# SCH_Control_Decoder_2021-10-07.net
KiCad netlist of a schematic drawn in EasyEDA
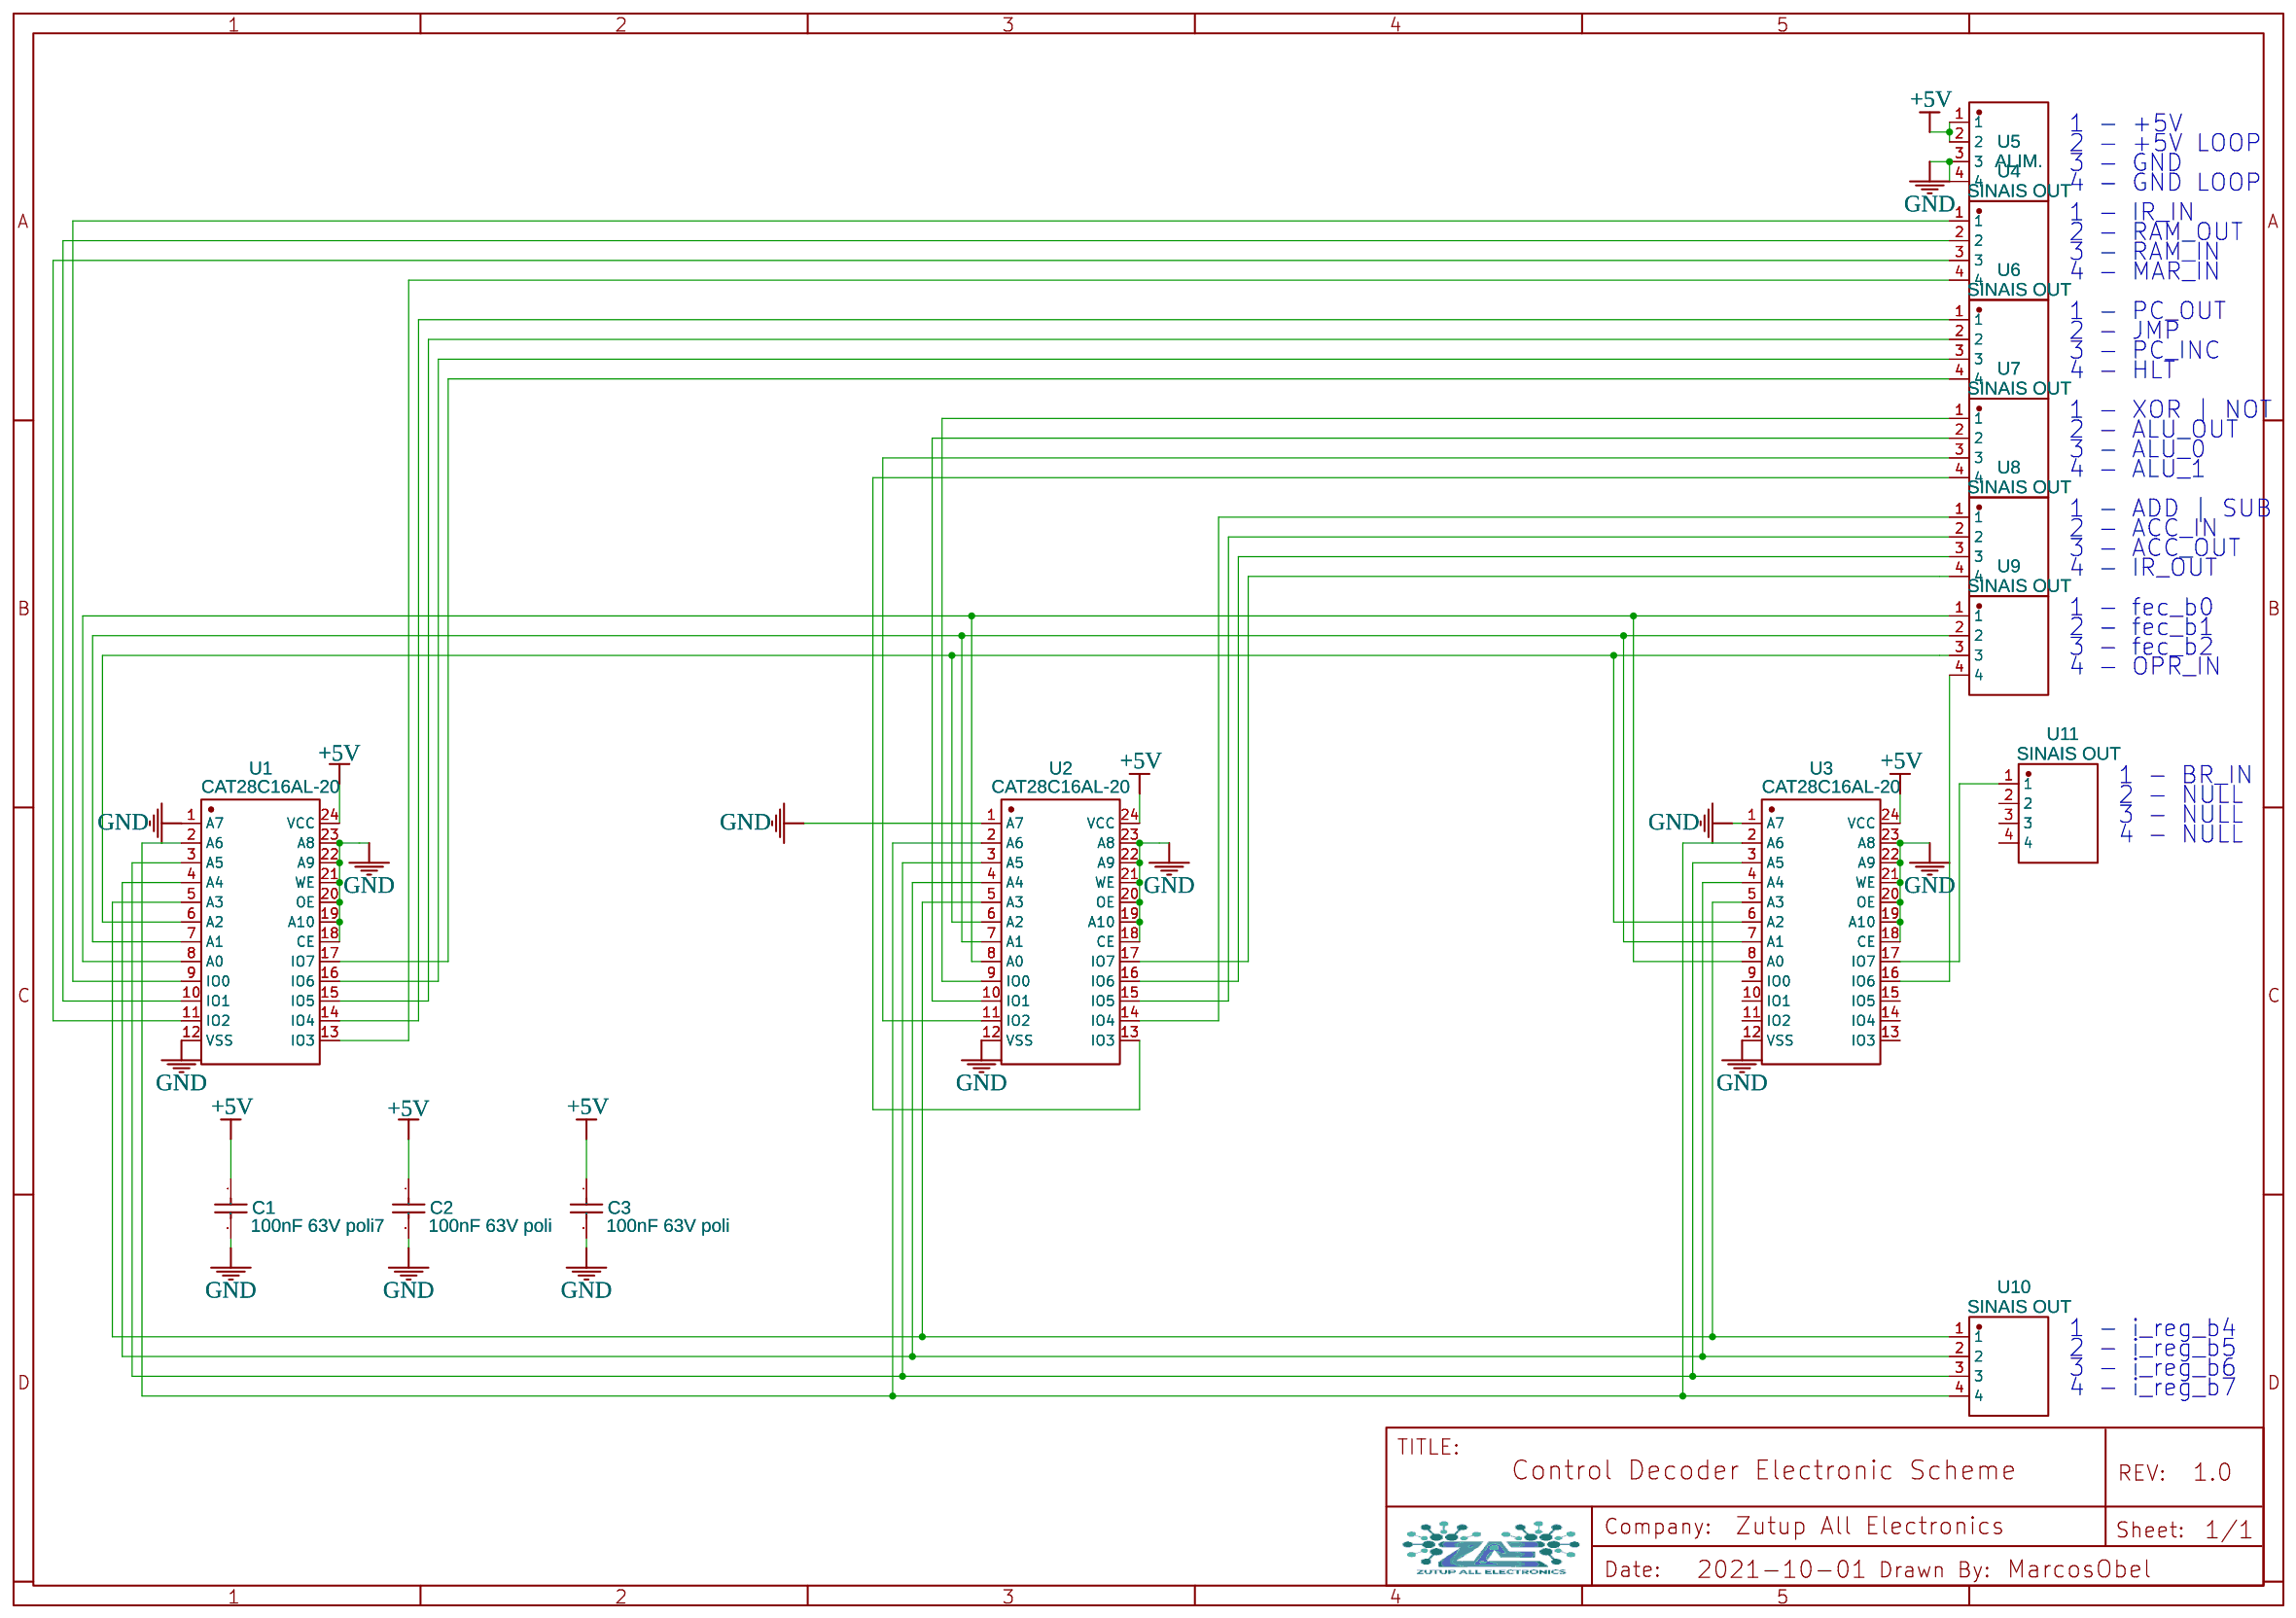
[diagram p0: schematic sheet]

(export (version "E")
  (design (tool "Eeschema 10.0.6"))
  (components
    (comp (ref "C1")
      (value "100nF 63V poli7")
      (fields
        (field (name "BOM_Manufacturer Part") "SR305C105KAR")
        (field (name "BOM_Supplier Part") "C444741")
      )
      (libsource (lib "") (part "SR305C105KAR"))
    )
    (comp (ref "C2")
      (value "100nF 63V poli")
      (fields
        (field (name "BOM_Manufacturer Part") "SR305C105KAR")
        (field (name "BOM_Supplier Part") "C444741")
      )
      (libsource (lib "") (part "SR305C105KAR"))
    )
    (comp (ref "C3")
      (value "100nF 63V poli")
      (fields
        (field (name "BOM_Manufacturer Part") "SR305C105KAR")
        (field (name "BOM_Supplier Part") "C444741")
      )
      (libsource (lib "") (part "SR305C105KAR"))
    )
    (comp (ref "U1") (value "CAT28C16AL-20") (libsource (lib "") (part "CAT28C16AL-20")))
    (comp (ref "U2") (value "CAT28C16AL-20") (libsource (lib "") (part "CAT28C16AL-20")))
    (comp (ref "U3") (value "CAT28C16AL-20") (libsource (lib "") (part "CAT28C16AL-20")))
    (comp (ref "U4")
      (value "SINAIS OUT")
      (fields (field (name "BOM_Manufacturer Part") "171825-4") (field (name "BOM_Supplier Part") "C210162"))
      (libsource (lib "") (part "171825-4"))
    )
    (comp (ref "U5")
      (value "ALIM.")
      (fields (field (name "BOM_Manufacturer Part") "171825-4") (field (name "BOM_Supplier Part") "C210162"))
      (libsource (lib "") (part "171825-4"))
    )
    (comp (ref "U6")
      (value "SINAIS OUT")
      (fields (field (name "BOM_Manufacturer Part") "171825-4") (field (name "BOM_Supplier Part") "C210162"))
      (libsource (lib "") (part "171825-4"))
    )
    (comp (ref "U7")
      (value "SINAIS OUT")
      (fields (field (name "BOM_Manufacturer Part") "171825-4") (field (name "BOM_Supplier Part") "C210162"))
      (libsource (lib "") (part "171825-4"))
    )
    (comp (ref "U8")
      (value "SINAIS OUT")
      (fields (field (name "BOM_Manufacturer Part") "171825-4") (field (name "BOM_Supplier Part") "C210162"))
      (libsource (lib "") (part "171825-4"))
    )
    (comp (ref "U9")
      (value "SINAIS OUT")
      (fields (field (name "BOM_Manufacturer Part") "171825-4") (field (name "BOM_Supplier Part") "C210162"))
      (libsource (lib "") (part "171825-4"))
    )
    (comp (ref "U10")
      (value "SINAIS OUT")
      (fields (field (name "BOM_Manufacturer Part") "171825-4") (field (name "BOM_Supplier Part") "C210162"))
      (libsource (lib "") (part "171825-4"))
    )
    (comp (ref "U11")
      (value "SINAIS OUT")
      (fields (field (name "BOM_Manufacturer Part") "171825-4") (field (name "BOM_Supplier Part") "C210162"))
      (libsource (lib "") (part "171825-4"))
    )
  )
  (nets
    (net (code "1") (name "+5V") (class "Default")
      (node (ref "C1") (pin "1") (pinfunction "1_1") (pintype "input"))
      (node (ref "C2") (pin "1") (pinfunction "1_1") (pintype "input"))
      (node (ref "C3") (pin "1") (pinfunction "1_1") (pintype "input"))
      (node (ref "U1") (pin "24") (pinfunction "VCC_24") (pintype "unspecified"))
      (node (ref "U2") (pin "24") (pinfunction "VCC_24") (pintype "unspecified"))
      (node (ref "U3") (pin "24") (pinfunction "VCC_24") (pintype "unspecified"))
      (node (ref "U5") (pin "1") (pinfunction "1_1") (pintype "unspecified"))
      (node (ref "U5") (pin "2") (pinfunction "2_2") (pintype "unspecified"))
    )
    (net (code "2") (name "GND") (class "Default")
      (node (ref "C1") (pin "2") (pinfunction "2_2") (pintype "input"))
      (node (ref "C2") (pin "2") (pinfunction "2_2") (pintype "input"))
      (node (ref "C3") (pin "2") (pinfunction "2_2") (pintype "input"))
      (node (ref "U1") (pin "1") (pinfunction "A7_1") (pintype "unspecified"))
      (node (ref "U1") (pin "12") (pinfunction "VSS_12") (pintype "unspecified"))
      (node (ref "U1") (pin "18") (pinfunction "CE_18") (pintype "unspecified"))
      (node (ref "U1") (pin "19") (pinfunction "A10_19") (pintype "unspecified"))
      (node (ref "U1") (pin "20") (pinfunction "OE_20") (pintype "unspecified"))
      (node (ref "U1") (pin "21") (pinfunction "WE_21") (pintype "unspecified"))
      (node (ref "U1") (pin "22") (pinfunction "A9_22") (pintype "unspecified"))
      (node (ref "U1") (pin "23") (pinfunction "A8_23") (pintype "unspecified"))
      (node (ref "U2") (pin "1") (pinfunction "A7_1") (pintype "unspecified"))
      (node (ref "U2") (pin "12") (pinfunction "VSS_12") (pintype "unspecified"))
      (node (ref "U2") (pin "18") (pinfunction "CE_18") (pintype "unspecified"))
      (node (ref "U2") (pin "19") (pinfunction "A10_19") (pintype "unspecified"))
      (node (ref "U2") (pin "20") (pinfunction "OE_20") (pintype "unspecified"))
      (node (ref "U2") (pin "21") (pinfunction "WE_21") (pintype "unspecified"))
      (node (ref "U2") (pin "22") (pinfunction "A9_22") (pintype "unspecified"))
      (node (ref "U2") (pin "23") (pinfunction "A8_23") (pintype "unspecified"))
      (node (ref "U3") (pin "1") (pinfunction "A7_1") (pintype "unspecified"))
      (node (ref "U3") (pin "12") (pinfunction "VSS_12") (pintype "unspecified"))
      (node (ref "U3") (pin "18") (pinfunction "CE_18") (pintype "unspecified"))
      (node (ref "U3") (pin "19") (pinfunction "A10_19") (pintype "unspecified"))
      (node (ref "U3") (pin "20") (pinfunction "OE_20") (pintype "unspecified"))
      (node (ref "U3") (pin "21") (pinfunction "WE_21") (pintype "unspecified"))
      (node (ref "U3") (pin "22") (pinfunction "A9_22") (pintype "unspecified"))
      (node (ref "U3") (pin "23") (pinfunction "A8_23") (pintype "unspecified"))
      (node (ref "U5") (pin "3") (pinfunction "3_3") (pintype "unspecified"))
      (node (ref "U5") (pin "4") (pinfunction "4_4") (pintype "unspecified"))
    )
    (net (code "3") (name "Net-(U1-A0)") (class "Default")
      (node (ref "U1") (pin "8") (pinfunction "A0_8") (pintype "unspecified"))
      (node (ref "U2") (pin "8") (pinfunction "A0_8") (pintype "unspecified"))
      (node (ref "U3") (pin "8") (pinfunction "A0_8") (pintype "unspecified"))
      (node (ref "U9") (pin "1") (pinfunction "1_1") (pintype "unspecified"))
    )
    (net (code "4") (name "Net-(U1-A1)") (class "Default")
      (node (ref "U1") (pin "7") (pinfunction "A1_7") (pintype "unspecified"))
      (node (ref "U2") (pin "7") (pinfunction "A1_7") (pintype "unspecified"))
      (node (ref "U3") (pin "7") (pinfunction "A1_7") (pintype "unspecified"))
      (node (ref "U9") (pin "2") (pinfunction "2_2") (pintype "unspecified"))
    )
    (net (code "5") (name "Net-(U1-A2)") (class "Default")
      (node (ref "U1") (pin "6") (pinfunction "A2_6") (pintype "unspecified"))
      (node (ref "U2") (pin "6") (pinfunction "A2_6") (pintype "unspecified"))
      (node (ref "U3") (pin "6") (pinfunction "A2_6") (pintype "unspecified"))
      (node (ref "U9") (pin "3") (pinfunction "3_3") (pintype "unspecified"))
    )
    (net (code "6") (name "Net-(U1-A3)") (class "Default")
      (node (ref "U1") (pin "5") (pinfunction "A3_5") (pintype "unspecified"))
      (node (ref "U10") (pin "1") (pinfunction "1_1") (pintype "unspecified"))
      (node (ref "U2") (pin "5") (pinfunction "A3_5") (pintype "unspecified"))
      (node (ref "U3") (pin "5") (pinfunction "A3_5") (pintype "unspecified"))
    )
    (net (code "7") (name "Net-(U1-A4)") (class "Default")
      (node (ref "U1") (pin "4") (pinfunction "A4_4") (pintype "unspecified"))
      (node (ref "U10") (pin "2") (pinfunction "2_2") (pintype "unspecified"))
      (node (ref "U2") (pin "4") (pinfunction "A4_4") (pintype "unspecified"))
      (node (ref "U3") (pin "4") (pinfunction "A4_4") (pintype "unspecified"))
    )
    (net (code "8") (name "Net-(U1-A5)") (class "Default")
      (node (ref "U1") (pin "3") (pinfunction "A5_3") (pintype "unspecified"))
      (node (ref "U10") (pin "3") (pinfunction "3_3") (pintype "unspecified"))
      (node (ref "U2") (pin "3") (pinfunction "A5_3") (pintype "unspecified"))
      (node (ref "U3") (pin "3") (pinfunction "A5_3") (pintype "unspecified"))
    )
    (net (code "9") (name "Net-(U1-A6)") (class "Default")
      (node (ref "U1") (pin "2") (pinfunction "A6_2") (pintype "unspecified"))
      (node (ref "U10") (pin "4") (pinfunction "4_4") (pintype "unspecified"))
      (node (ref "U2") (pin "2") (pinfunction "A6_2") (pintype "unspecified"))
      (node (ref "U3") (pin "2") (pinfunction "A6_2") (pintype "unspecified"))
    )
    (net (code "10") (name "Net-(U1-IO0)") (class "Default")
      (node (ref "U1") (pin "9") (pinfunction "IO0_9") (pintype "unspecified"))
      (node (ref "U4") (pin "1") (pinfunction "1_1") (pintype "unspecified"))
    )
    (net (code "11") (name "Net-(U1-IO1)") (class "Default")
      (node (ref "U1") (pin "10") (pinfunction "IO1_10") (pintype "unspecified"))
      (node (ref "U4") (pin "2") (pinfunction "2_2") (pintype "unspecified"))
    )
    (net (code "12") (name "Net-(U1-IO2)") (class "Default")
      (node (ref "U1") (pin "11") (pinfunction "IO2_11") (pintype "unspecified"))
      (node (ref "U4") (pin "3") (pinfunction "3_3") (pintype "unspecified"))
    )
    (net (code "13") (name "Net-(U1-IO3)") (class "Default")
      (node (ref "U1") (pin "13") (pinfunction "IO3_13") (pintype "unspecified"))
      (node (ref "U4") (pin "4") (pinfunction "4_4") (pintype "unspecified"))
    )
    (net (code "14") (name "Net-(U1-IO4)") (class "Default")
      (node (ref "U1") (pin "14") (pinfunction "IO4_14") (pintype "unspecified"))
      (node (ref "U6") (pin "1") (pinfunction "1_1") (pintype "unspecified"))
    )
    (net (code "15") (name "Net-(U1-IO5)") (class "Default")
      (node (ref "U1") (pin "15") (pinfunction "IO5_15") (pintype "unspecified"))
      (node (ref "U6") (pin "2") (pinfunction "2_2") (pintype "unspecified"))
    )
    (net (code "16") (name "Net-(U1-IO6)") (class "Default")
      (node (ref "U1") (pin "16") (pinfunction "IO6_16") (pintype "unspecified"))
      (node (ref "U6") (pin "3") (pinfunction "3_3") (pintype "unspecified"))
    )
    (net (code "17") (name "Net-(U1-IO7)") (class "Default")
      (node (ref "U1") (pin "17") (pinfunction "IO7_17") (pintype "unspecified"))
      (node (ref "U6") (pin "4") (pinfunction "4_4") (pintype "unspecified"))
    )
    (net (code "18") (name "Net-(U2-IO0)") (class "Default")
      (node (ref "U2") (pin "9") (pinfunction "IO0_9") (pintype "unspecified"))
      (node (ref "U7") (pin "1") (pinfunction "1_1") (pintype "unspecified"))
    )
    (net (code "19") (name "Net-(U2-IO1)") (class "Default")
      (node (ref "U2") (pin "10") (pinfunction "IO1_10") (pintype "unspecified"))
      (node (ref "U7") (pin "2") (pinfunction "2_2") (pintype "unspecified"))
    )
    (net (code "20") (name "Net-(U2-IO2)") (class "Default")
      (node (ref "U2") (pin "11") (pinfunction "IO2_11") (pintype "unspecified"))
      (node (ref "U7") (pin "3") (pinfunction "3_3") (pintype "unspecified"))
    )
    (net (code "21") (name "Net-(U2-IO3)") (class "Default")
      (node (ref "U2") (pin "13") (pinfunction "IO3_13") (pintype "unspecified"))
      (node (ref "U7") (pin "4") (pinfunction "4_4") (pintype "unspecified"))
    )
    (net (code "22") (name "Net-(U2-IO4)") (class "Default")
      (node (ref "U2") (pin "14") (pinfunction "IO4_14") (pintype "unspecified"))
      (node (ref "U8") (pin "1") (pinfunction "1_1") (pintype "unspecified"))
    )
    (net (code "23") (name "Net-(U2-IO5)") (class "Default")
      (node (ref "U2") (pin "15") (pinfunction "IO5_15") (pintype "unspecified"))
      (node (ref "U8") (pin "2") (pinfunction "2_2") (pintype "unspecified"))
    )
    (net (code "24") (name "Net-(U2-IO6)") (class "Default")
      (node (ref "U2") (pin "16") (pinfunction "IO6_16") (pintype "unspecified"))
      (node (ref "U8") (pin "3") (pinfunction "3_3") (pintype "unspecified"))
    )
    (net (code "25") (name "Net-(U2-IO7)") (class "Default")
      (node (ref "U2") (pin "17") (pinfunction "IO7_17") (pintype "unspecified"))
      (node (ref "U8") (pin "4") (pinfunction "4_4") (pintype "unspecified"))
    )
    (net (code "26") (name "Net-(U3-IO6)") (class "Default")
      (node (ref "U3") (pin "16") (pinfunction "IO6_16") (pintype "unspecified"))
      (node (ref "U9") (pin "4") (pinfunction "4_4") (pintype "unspecified"))
    )
    (net (code "27") (name "Net-(U3-IO7)") (class "Default")
      (node (ref "U11") (pin "1") (pinfunction "1_1") (pintype "unspecified"))
      (node (ref "U3") (pin "17") (pinfunction "IO7_17") (pintype "unspecified"))
    )
    (net (code "28") (name "unconnected-(U3-IO0-Pad9)") (class "Default")
      (node (ref "U3") (pin "9") (pinfunction "IO0_9") (pintype "unspecified"))
    )
    (net (code "29") (name "unconnected-(U3-IO1-Pad10)") (class "Default")
      (node (ref "U3") (pin "10") (pinfunction "IO1_10") (pintype "unspecified"))
    )
    (net (code "30") (name "unconnected-(U3-IO2-Pad11)") (class "Default")
      (node (ref "U3") (pin "11") (pinfunction "IO2_11") (pintype "unspecified"))
    )
    (net (code "31") (name "unconnected-(U3-IO3-Pad13)") (class "Default")
      (node (ref "U3") (pin "13") (pinfunction "IO3_13") (pintype "unspecified"))
    )
    (net (code "32") (name "unconnected-(U3-IO4-Pad14)") (class "Default")
      (node (ref "U3") (pin "14") (pinfunction "IO4_14") (pintype "unspecified"))
    )
    (net (code "33") (name "unconnected-(U3-IO5-Pad15)") (class "Default")
      (node (ref "U3") (pin "15") (pinfunction "IO5_15") (pintype "unspecified"))
    )
    (net (code "34") (name "unconnected-(U11-Pad2)") (class "Default")
      (node (ref "U11") (pin "2") (pinfunction "2_2") (pintype "unspecified"))
    )
    (net (code "35") (name "unconnected-(U11-Pad3)") (class "Default")
      (node (ref "U11") (pin "3") (pinfunction "3_3") (pintype "unspecified"))
    )
    (net (code "36") (name "unconnected-(U11-Pad4)") (class "Default")
      (node (ref "U11") (pin "4") (pinfunction "4_4") (pintype "unspecified"))
    )
  )
)
